# greenhousectrl-latest.net
KiCad netlist of a schematic drawn in EAGLE
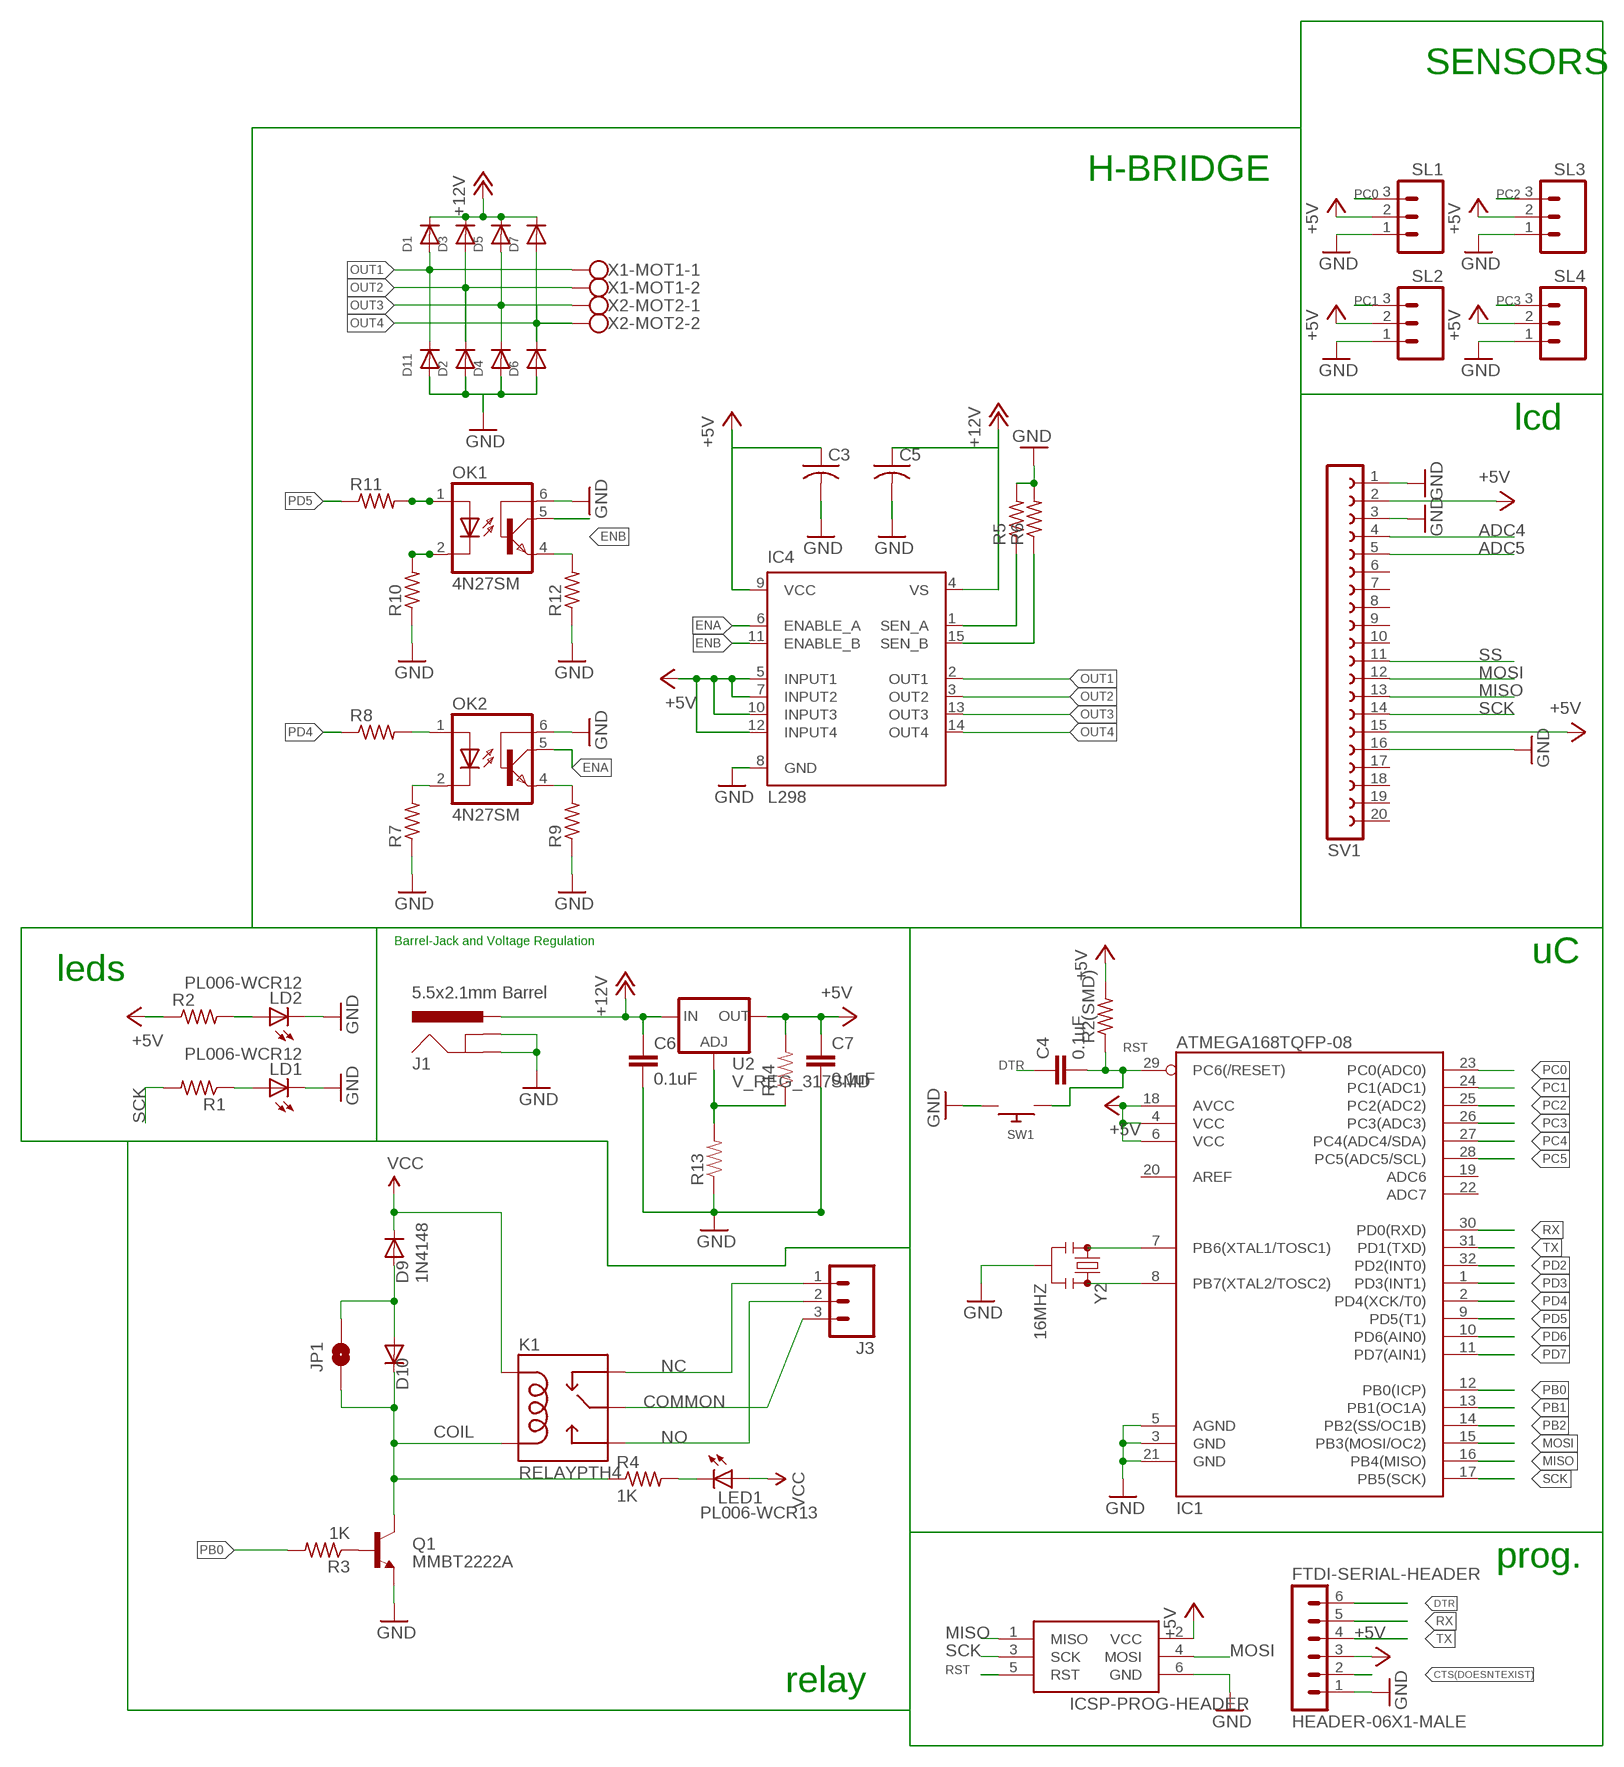
[diagram p0: schematic, sheet 1]

(export (version "E")
  (design (tool "Eeschema 10.0.6"))
  (components
    (comp (ref "C3")
      (value "C-US025-024X044")
      (footprint "eagle-import:C025-024X044")
      (libsource (lib "eagle-import") (part "C-US025-024X044"))
    )
    (comp (ref "C4")
      (value "0.1uF")
      (footprint "eagle-import:0603-CAP")
      (libsource (lib "eagle-import") (part "0.1UF-25V(+80/-20%)(0603)"))
    )
    (comp (ref "C5")
      (value "C-US025-024X044")
      (footprint "eagle-import:C025-024X044")
      (libsource (lib "eagle-import") (part "C-US025-024X044"))
    )
    (comp (ref "C6")
      (value "0.1uF")
      (footprint "eagle-import:0603-CAP")
      (libsource (lib "eagle-import") (part "0.1UF-25V(+80/-20%)(0603)"))
    )
    (comp (ref "C7")
      (value "0.1uF")
      (footprint "eagle-import:0603-CAP")
      (libsource (lib "eagle-import") (part "0.1UF-25V(+80/-20%)(0603)"))
    )
    (comp (ref "D1")
      (value "DIODESOD-523")
      (footprint "eagle-import:SOD-523")
      (libsource (lib "eagle-import") (part "DIODESOD-523"))
    )
    (comp (ref "D2")
      (value "DIODESOD-523")
      (footprint "eagle-import:SOD-523")
      (libsource (lib "eagle-import") (part "DIODESOD-523"))
    )
    (comp (ref "D3")
      (value "DIODESOD-523")
      (footprint "eagle-import:SOD-523")
      (libsource (lib "eagle-import") (part "DIODESOD-523"))
    )
    (comp (ref "D4")
      (value "DIODESOD-523")
      (footprint "eagle-import:SOD-523")
      (libsource (lib "eagle-import") (part "DIODESOD-523"))
    )
    (comp (ref "D5")
      (value "DIODESOD-523")
      (footprint "eagle-import:SOD-523")
      (libsource (lib "eagle-import") (part "DIODESOD-523"))
    )
    (comp (ref "D6")
      (value "DIODESOD-523")
      (footprint "eagle-import:SOD-523")
      (libsource (lib "eagle-import") (part "DIODESOD-523"))
    )
    (comp (ref "D7")
      (value "DIODESOD-523")
      (footprint "eagle-import:SOD-523")
      (libsource (lib "eagle-import") (part "DIODESOD-523"))
    )
    (comp (ref "D9")
      (value "1N4148")
      (footprint "eagle-import:SOD-323F")
      (libsource (lib "eagle-import") (part "DIODESOD-323F"))
    )
    (comp (ref "D10")
      (value "Zener")
      (footprint "eagle-import:SOD-323F")
      (libsource (lib "eagle-import") (part "DIODESOD-323F"))
    )
    (comp (ref "D11")
      (value "DIODESOD-523")
      (footprint "eagle-import:SOD-523")
      (libsource (lib "eagle-import") (part "DIODESOD-523"))
    )
    (comp (ref "FTDI-SERIAL-HEADER")
      (value "HEADER-06X1-MALE")
      (footprint "eagle-import:06X1-PTH")
      (libsource (lib "eagle-import") (part "HEADER-06X1?-MALE"))
    )
    (comp (ref "IC1")
      (value "ATMEGA168TQFP-08")
      (footprint "eagle-import:TQFP32-08")
      (libsource (lib "eagle-import") (part "ATMEGA168TQFP-08"))
    )
    (comp (ref "IC4")
      (value "L298")
      (footprint "eagle-import:MULTIWATT-15")
      (fields (field (name "MPN") "L298N"))
      (libsource (lib "eagle-import") (part "L298"))
    )
    (comp (ref "ICSP-PROG-HEADER")
      (value "AVRISP-6")
      (footprint "eagle-import:AVRISP")
      (libsource (lib "eagle-import") (part "AVRISP-6"))
    )
    (comp (ref "J1")
      (value "5.5x2.1mm Barrel")
      (footprint "eagle-import:POWER_JACK_SMD")
      (libsource (lib "eagle-import") (part "POWER_JACKSMD"))
    )
    (comp (ref "J3")
      (value "M03-SCREW-5MM")
      (footprint "eagle-import:SCREWTERMINAL-5MM-3")
      (libsource (lib "eagle-import") (part "M03-SCREW-5MM"))
    )
    (comp (ref "JP1")
      (value "JUMPER-PAD-2-NOYES_SILK")
      (footprint "eagle-import:PAD-JUMPER-2-NO_YES_SILK")
      (libsource (lib "eagle-import") (part "JUMPER-PAD-2-NOYES_SILK"))
    )
    (comp (ref "K1")
      (value "RELAYPTH4")
      (footprint "eagle-import:RELAY-JZC")
      (libsource (lib "eagle-import") (part "RELAYPTH4"))
    )
    (comp (ref "LD1")
      (value "PL006-WCR12")
      (footprint "eagle-import:SOT23")
      (libsource (lib "eagle-import") (part "PL006-WCR12"))
    )
    (comp (ref "LD2")
      (value "PL006-WCR12")
      (footprint "eagle-import:SOT23")
      (libsource (lib "eagle-import") (part "PL006-WCR12"))
    )
    (comp (ref "LED1")
      (value "PL006-WCR13")
      (footprint "eagle-import:SOT23")
      (fields (field (name "PROD_ID") "DIO-09529"))
      (libsource (lib "eagle-import") (part "PL006-WCR13"))
    )
    (comp (ref "OK1")
      (value "4N27SM")
      (footprint "eagle-import:DIL6-SMD")
      (fields (field (name "MF") "FAIRCHILD SEMICONDUCTOR") (field (name "MPN") "4N27S-M"))
      (libsource (lib "eagle-import") (part "4N?MS27"))
    )
    (comp (ref "OK2")
      (value "4N27SM")
      (footprint "eagle-import:DIL6-SMD")
      (fields (field (name "MF") "FAIRCHILD SEMICONDUCTOR") (field (name "MPN") "4N27S-M"))
      (libsource (lib "eagle-import") (part "4N?MS27"))
    )
    (comp (ref "Q1")
      (value "MMBT2222A")
      (footprint "eagle-import:SOT23-3")
      (libsource (lib "eagle-import") (part "TRANSISTOR_NPNMMBT2222A"))
    )
    (comp (ref "R1")
      (value "R-US_M0805")
      (footprint "eagle-import:M0805")
      (libsource (lib "eagle-import") (part "R-US_M0805"))
    )
    (comp (ref "R2")
      (value "R-US_M0805")
      (footprint "eagle-import:M0805")
      (libsource (lib "eagle-import") (part "R-US_M0805"))
    )
    (comp (ref "R2(SMD)")
      (value "R-US_M0805")
      (footprint "eagle-import:M0805")
      (libsource (lib "eagle-import") (part "R-US_M0805"))
    )
    (comp (ref "R3")
      (value "1K")
      (footprint "eagle-import:M0805")
      (libsource (lib "eagle-import") (part "R-US_M0805"))
    )
    (comp (ref "R4")
      (value "1K")
      (footprint "eagle-import:M0805")
      (libsource (lib "eagle-import") (part "R-US_M0805"))
    )
    (comp (ref "R5")
      (value "R-US_M0805")
      (footprint "eagle-import:M0805")
      (libsource (lib "eagle-import") (part "R-US_M0805"))
    )
    (comp (ref "R6")
      (value "R-US_M0805")
      (footprint "eagle-import:M0805")
      (libsource (lib "eagle-import") (part "R-US_M0805"))
    )
    (comp (ref "R7")
      (value "R-US_M0805")
      (footprint "eagle-import:M0805")
      (libsource (lib "eagle-import") (part "R-US_M0805"))
    )
    (comp (ref "R8")
      (value "R-US_M0805")
      (footprint "eagle-import:M0805")
      (libsource (lib "eagle-import") (part "R-US_M0805"))
    )
    (comp (ref "R9")
      (value "R-US_M0805")
      (footprint "eagle-import:M0805")
      (libsource (lib "eagle-import") (part "R-US_M0805"))
    )
    (comp (ref "R10")
      (value "R-US_M0805")
      (footprint "eagle-import:M0805")
      (libsource (lib "eagle-import") (part "R-US_M0805"))
    )
    (comp (ref "R11")
      (value "R-US_M0805")
      (footprint "eagle-import:M0805")
      (libsource (lib "eagle-import") (part "R-US_M0805"))
    )
    (comp (ref "R12")
      (value "R-US_M0805")
      (footprint "eagle-import:M0805")
      (libsource (lib "eagle-import") (part "R-US_M0805"))
    )
    (comp (ref "R13")
      (value "RESISTOR0402")
      (footprint "eagle-import:0402-RES")
      (libsource (lib "eagle-import") (part "RESISTOR0402"))
    )
    (comp (ref "R14")
      (value "RESISTOR0402")
      (footprint "eagle-import:0402-RES")
      (libsource (lib "eagle-import") (part "RESISTOR0402"))
    )
    (comp (ref "SL1")
      (value "M03")
      (footprint "eagle-import:03P")
      (libsource (lib "eagle-import") (part "M03"))
    )
    (comp (ref "SL2")
      (value "M03")
      (footprint "eagle-import:03P")
      (libsource (lib "eagle-import") (part "M03"))
    )
    (comp (ref "SL3")
      (value "M03")
      (footprint "eagle-import:03P")
      (libsource (lib "eagle-import") (part "M03"))
    )
    (comp (ref "SL4")
      (value "M03")
      (footprint "eagle-import:03P")
      (libsource (lib "eagle-import") (part "M03"))
    )
    (comp (ref "SV1")
      (value "FE20-1")
      (footprint "eagle-import:FE20")
      (libsource (lib "eagle-import") (part "FE20-1"))
    )
    (comp (ref "SW1")
      (value "SWITCH_PUSHBUTTONC&K_KSS")
      (footprint "eagle-import:BTN_CK_KSS")
      (libsource (lib "eagle-import") (part "SWITCH_PUSHBUTTONC&K_KSS"))
    )
    (comp (ref "U2")
      (value "V_REG_317SMD")
      (footprint "eagle-import:SOT223")
      (libsource (lib "eagle-import") (part "V_REG_317SMD"))
    )
    (comp (ref "X1-MOT1")
      (value "W237-102")
      (footprint "eagle-import:W237-102")
      (fields (field (name "MPN") "237-102"))
      (libsource (lib "eagle-import") (part "W237-102"))
    )
    (comp (ref "X2-MOT2")
      (value "W237-102")
      (footprint "eagle-import:W237-102")
      (fields (field (name "MPN") "237-102"))
      (libsource (lib "eagle-import") (part "W237-102"))
    )
    (comp (ref "Y2")
      (value "16MHZ")
      (footprint "eagle-import:RESONATOR-SMD")
      (libsource (lib "eagle-import") (part "RESONATOR16MHZ"))
    )
  )
  (nets
    (net (code "1") (name "+5V") (class "Default")
      (node (ref "C3") (pin "1") (pinfunction "1_1") (pintype "passive"))
      (node (ref "C7") (pin "1") (pinfunction "1_1") (pintype "passive"))
      (node (ref "FTDI-SERIAL-HEADER") (pin "3") (pinfunction "3_3") (pintype "passive"))
      (node (ref "IC1") (pin "18") (pinfunction "AVCC_18") (pintype "bidirectional"))
      (node (ref "IC1") (pin "4") (pinfunction "VCC_4") (pintype "bidirectional"))
      (node (ref "IC1") (pin "6") (pinfunction "VCC_6") (pintype "bidirectional"))
      (node (ref "IC4") (pin "10") (pinfunction "INPUT3_10") (pintype "input"))
      (node (ref "IC4") (pin "12") (pinfunction "INPUT4_12") (pintype "input"))
      (node (ref "IC4") (pin "5") (pinfunction "INPUT1_5") (pintype "input"))
      (node (ref "IC4") (pin "7") (pinfunction "INPUT2_7") (pintype "input"))
      (node (ref "IC4") (pin "9") (pinfunction "VCC_9") (pintype "power_in"))
      (node (ref "ICSP-PROG-HEADER") (pin "2") (pinfunction "VCC_2") (pintype "power_in"))
      (node (ref "R14") (pin "2") (pinfunction "2_2") (pintype "passive"))
      (node (ref "R2") (pin "1") (pinfunction "1_1") (pintype "passive"))
      (node (ref "R2(SMD)") (pin "2") (pinfunction "2_2") (pintype "passive"))
      (node (ref "SL1") (pin "2") (pinfunction "2_2") (pintype "passive"))
      (node (ref "SL2") (pin "2") (pinfunction "2_2") (pintype "passive"))
      (node (ref "SL3") (pin "2") (pinfunction "2_2") (pintype "passive"))
      (node (ref "SL4") (pin "2") (pinfunction "2_2") (pintype "passive"))
      (node (ref "SV1") (pin "15") (pinfunction "15_15") (pintype "passive"))
      (node (ref "SV1") (pin "2") (pinfunction "2_2") (pintype "passive"))
      (node (ref "U2") (pin "2") (pinfunction "OUT_2") (pintype "output"))
    )
    (net (code "2") (name "+12V") (class "Default")
      (node (ref "C5") (pin "1") (pinfunction "1_1") (pintype "passive"))
      (node (ref "C6") (pin "1") (pinfunction "1_1") (pintype "passive"))
      (node (ref "D1") (pin "K") (pinfunction "C_K") (pintype "passive"))
      (node (ref "D3") (pin "K") (pinfunction "C_K") (pintype "passive"))
      (node (ref "D5") (pin "K") (pinfunction "C_K") (pintype "passive"))
      (node (ref "D7") (pin "K") (pinfunction "C_K") (pintype "passive"))
      (node (ref "IC4") (pin "4") (pinfunction "VS_4") (pintype "power_in"))
      (node (ref "J1") (pin "VIN0") (pinfunction "PWR_VIN0") (pintype "bidirectional"))
      (node (ref "U2") (pin "3") (pinfunction "IN_3") (pintype "input"))
    )
    (net (code "3") (name "/ADC4") (class "Default")
      (node (ref "SV1") (pin "4") (pinfunction "4_4") (pintype "passive"))
    )
    (net (code "4") (name "/ADC5") (class "Default")
      (node (ref "SV1") (pin "5") (pinfunction "5_5") (pintype "passive"))
    )
    (net (code "5") (name "/COIL") (class "Default")
      (node (ref "D10") (pin "C") (pinfunction "C_C") (pintype "passive"))
      (node (ref "JP1") (pin "1") (pinfunction "1_1") (pintype "passive"))
      (node (ref "K1") (pin "1") (pinfunction "COIL2_1") (pintype "bidirectional"))
      (node (ref "Q1") (pin "3") (pinfunction "C_3") (pintype "passive"))
      (node (ref "R4") (pin "1") (pinfunction "1_1") (pintype "passive"))
    )
    (net (code "6") (name "/COMMON") (class "Default")
      (node (ref "J3") (pin "3") (pinfunction "3_3") (pintype "passive"))
      (node (ref "K1") (pin "4") (pinfunction "MAIN_4") (pintype "bidirectional"))
    )
    (net (code "7") (name "/NC") (class "Default")
      (node (ref "J3") (pin "1") (pinfunction "1_1") (pintype "passive"))
      (node (ref "K1") (pin "2") (pinfunction "NC_2") (pintype "bidirectional"))
    )
    (net (code "8") (name "/NO") (class "Default")
      (node (ref "J3") (pin "2") (pinfunction "2_2") (pintype "passive"))
      (node (ref "K1") (pin "3") (pinfunction "NO_3") (pintype "bidirectional"))
    )
    (net (code "9") (name "/RST") (class "Default")
      (node (ref "C4") (pin "2") (pinfunction "2_2") (pintype "passive"))
      (node (ref "IC1") (pin "29") (pinfunction "PC6(/RESET)_29") (pintype "bidirectional"))
      (node (ref "ICSP-PROG-HEADER") (pin "5") (pinfunction "RST_5") (pintype "output"))
      (node (ref "R2(SMD)") (pin "1") (pinfunction "1_1") (pintype "passive"))
      (node (ref "SW1") (pin "P$1") (pinfunction "P$1_P$1") (pintype "passive"))
    )
    (net (code "10") (name "/SS") (class "Default")
      (node (ref "SV1") (pin "11") (pinfunction "11_11") (pintype "passive"))
    )
    (net (code "11") (name "CTS(DOESNTEXIST)") (class "Default")
      (node (ref "FTDI-SERIAL-HEADER") (pin "2") (pinfunction "2_2") (pintype "passive"))
    )
    (net (code "12") (name "DTR") (class "Default")
      (node (ref "C4") (pin "1") (pinfunction "1_1") (pintype "passive"))
      (node (ref "FTDI-SERIAL-HEADER") (pin "6") (pinfunction "6_6") (pintype "passive"))
    )
    (net (code "13") (name "ENA") (class "Default")
      (node (ref "IC4") (pin "6") (pinfunction "ENABLE_A_6") (pintype "input"))
      (node (ref "OK2") (pin "5") (pinfunction "COL_5") (pintype "passive"))
    )
    (net (code "14") (name "ENB") (class "Default")
      (node (ref "IC4") (pin "11") (pinfunction "ENABLE_B_11") (pintype "input"))
      (node (ref "OK1") (pin "5") (pinfunction "COL_5") (pintype "passive"))
    )
    (net (code "15") (name "GND") (class "Default")
      (node (ref "C3") (pin "2") (pinfunction "2_2") (pintype "passive"))
      (node (ref "C5") (pin "2") (pinfunction "2_2") (pintype "passive"))
      (node (ref "C6") (pin "2") (pinfunction "2_2") (pintype "passive"))
      (node (ref "C7") (pin "2") (pinfunction "2_2") (pintype "passive"))
      (node (ref "D11") (pin "A") (pinfunction "A_A") (pintype "passive"))
      (node (ref "D2") (pin "A") (pinfunction "A_A") (pintype "passive"))
      (node (ref "D4") (pin "A") (pinfunction "A_A") (pintype "passive"))
      (node (ref "D6") (pin "A") (pinfunction "A_A") (pintype "passive"))
      (node (ref "FTDI-SERIAL-HEADER") (pin "1") (pinfunction "1_1") (pintype "passive"))
      (node (ref "IC1") (pin "21") (pinfunction "GND_21") (pintype "bidirectional"))
      (node (ref "IC1") (pin "3") (pinfunction "GND_3") (pintype "bidirectional"))
      (node (ref "IC1") (pin "5") (pinfunction "AGND_5") (pintype "bidirectional"))
      (node (ref "IC4") (pin "8") (pinfunction "GND_8") (pintype "power_in"))
      (node (ref "ICSP-PROG-HEADER") (pin "6") (pinfunction "GND_6") (pintype "power_in"))
      (node (ref "J1") (pin "GND") (pinfunction "GNDBREAK_GND") (pintype "bidirectional"))
      (node (ref "J1") (pin "P$4") (pinfunction "GND_P$4") (pintype "bidirectional"))
      (node (ref "LD1") (pin "3") (pinfunction "C_3") (pintype "passive"))
      (node (ref "LD2") (pin "3") (pinfunction "C_3") (pintype "passive"))
      (node (ref "OK1") (pin "6") (pinfunction "BAS_6") (pintype "passive"))
      (node (ref "OK2") (pin "6") (pinfunction "BAS_6") (pintype "passive"))
      (node (ref "Q1") (pin "2") (pinfunction "E_2") (pintype "passive"))
      (node (ref "R10") (pin "1") (pinfunction "1_1") (pintype "passive"))
      (node (ref "R12") (pin "1") (pinfunction "1_1") (pintype "passive"))
      (node (ref "R13") (pin "1") (pinfunction "1_1") (pintype "passive"))
      (node (ref "R5") (pin "2") (pinfunction "2_2") (pintype "passive"))
      (node (ref "R6") (pin "2") (pinfunction "2_2") (pintype "passive"))
      (node (ref "R7") (pin "1") (pinfunction "1_1") (pintype "passive"))
      (node (ref "R9") (pin "1") (pinfunction "1_1") (pintype "passive"))
      (node (ref "SL1") (pin "1") (pinfunction "1_1") (pintype "passive"))
      (node (ref "SL2") (pin "1") (pinfunction "1_1") (pintype "passive"))
      (node (ref "SL3") (pin "1") (pinfunction "1_1") (pintype "passive"))
      (node (ref "SL4") (pin "1") (pinfunction "1_1") (pintype "passive"))
      (node (ref "SV1") (pin "1") (pinfunction "1_1") (pintype "passive"))
      (node (ref "SV1") (pin "16") (pinfunction "16_16") (pintype "passive"))
      (node (ref "SV1") (pin "3") (pinfunction "3_3") (pintype "passive"))
      (node (ref "SW1") (pin "P$2") (pinfunction "P$2_P$2") (pintype "passive"))
      (node (ref "Y2") (pin "2") (pinfunction "2_2") (pintype "passive"))
    )
    (net (code "16") (name "MISO") (class "Default")
      (node (ref "IC1") (pin "16") (pinfunction "PB4(MISO)_16") (pintype "bidirectional"))
      (node (ref "ICSP-PROG-HEADER") (pin "1") (pinfunction "MISO_1") (pintype "input"))
      (node (ref "SV1") (pin "13") (pinfunction "13_13") (pintype "passive"))
    )
    (net (code "17") (name "MOSI") (class "Default")
      (node (ref "IC1") (pin "15") (pinfunction "PB3(MOSI/OC2)_15") (pintype "bidirectional"))
      (node (ref "ICSP-PROG-HEADER") (pin "4") (pinfunction "MOSI_4") (pintype "output"))
      (node (ref "SV1") (pin "12") (pinfunction "12_12") (pintype "passive"))
    )
    (net (code "18") (name "Net-(D10-PadA)") (class "Default")
      (node (ref "D10") (pin "A") (pinfunction "A_A") (pintype "passive"))
      (node (ref "D9") (pin "A") (pinfunction "A_A") (pintype "passive"))
      (node (ref "JP1") (pin "2") (pinfunction "2_2") (pintype "passive"))
    )
    (net (code "19") (name "Net-(IC1-PB6(XTAL1{slash}TOSC1))") (class "Default")
      (node (ref "IC1") (pin "7") (pinfunction "PB6(XTAL1/TOSC1)_7") (pintype "bidirectional"))
      (node (ref "Y2") (pin "1") (pinfunction "1_1") (pintype "passive"))
    )
    (net (code "20") (name "Net-(IC1-PB7(XTAL2{slash}TOSC2))") (class "Default")
      (node (ref "IC1") (pin "8") (pinfunction "PB7(XTAL2/TOSC2)_8") (pintype "bidirectional"))
      (node (ref "Y2") (pin "3") (pinfunction "3_3") (pintype "passive"))
    )
    (net (code "21") (name "Net-(IC4-SEN_A)") (class "Default")
      (node (ref "IC4") (pin "1") (pinfunction "SEN_A_1") (pintype "input"))
      (node (ref "R5") (pin "1") (pinfunction "1_1") (pintype "passive"))
    )
    (net (code "22") (name "Net-(IC4-SEN_B)") (class "Default")
      (node (ref "IC4") (pin "15") (pinfunction "SEN_B_15") (pintype "input"))
      (node (ref "R6") (pin "1") (pinfunction "1_1") (pintype "passive"))
    )
    (net (code "23") (name "Net-(LD1-A)") (class "Default")
      (node (ref "LD1") (pin "1") (pinfunction "A_1") (pintype "passive"))
      (node (ref "R1") (pin "1") (pinfunction "1_1") (pintype "passive"))
    )
    (net (code "24") (name "Net-(LD2-A)") (class "Default")
      (node (ref "LD2") (pin "1") (pinfunction "A_1") (pintype "passive"))
      (node (ref "R2") (pin "2") (pinfunction "2_2") (pintype "passive"))
    )
    (net (code "25") (name "Net-(LED1-C)") (class "Default")
      (node (ref "LED1") (pin "3") (pinfunction "C_3") (pintype "passive"))
      (node (ref "R4") (pin "2") (pinfunction "2_2") (pintype "passive"))
    )
    (net (code "26") (name "Net-(OK1-A)") (class "Default")
      (node (ref "OK1") (pin "1") (pinfunction "A_1") (pintype "passive"))
      (node (ref "R11") (pin "2") (pinfunction "2_2") (pintype "passive"))
    )
    (net (code "27") (name "Net-(OK1-C)") (class "Default")
      (node (ref "OK1") (pin "2") (pinfunction "C_2") (pintype "passive"))
      (node (ref "R10") (pin "2") (pinfunction "2_2") (pintype "passive"))
    )
    (net (code "28") (name "Net-(OK1-EMI)") (class "Default")
      (node (ref "OK1") (pin "4") (pinfunction "EMI_4") (pintype "passive"))
      (node (ref "R12") (pin "2") (pinfunction "2_2") (pintype "passive"))
    )
    (net (code "29") (name "Net-(OK2-A)") (class "Default")
      (node (ref "OK2") (pin "1") (pinfunction "A_1") (pintype "passive"))
      (node (ref "R8") (pin "2") (pinfunction "2_2") (pintype "passive"))
    )
    (net (code "30") (name "Net-(OK2-C)") (class "Default")
      (node (ref "OK2") (pin "2") (pinfunction "C_2") (pintype "passive"))
      (node (ref "R7") (pin "2") (pinfunction "2_2") (pintype "passive"))
    )
    (net (code "31") (name "Net-(OK2-EMI)") (class "Default")
      (node (ref "OK2") (pin "4") (pinfunction "EMI_4") (pintype "passive"))
      (node (ref "R9") (pin "2") (pinfunction "2_2") (pintype "passive"))
    )
    (net (code "32") (name "Net-(Q1-B)") (class "Default")
      (node (ref "Q1") (pin "1") (pinfunction "B_1") (pintype "passive"))
      (node (ref "R3") (pin "1") (pinfunction "1_1") (pintype "passive"))
    )
    (net (code "33") (name "Net-(U2-ADJ)") (class "Default")
      (node (ref "R13") (pin "2") (pinfunction "2_2") (pintype "passive"))
      (node (ref "R14") (pin "1") (pinfunction "1_1") (pintype "passive"))
      (node (ref "U2") (pin "1") (pinfunction "ADJ_1") (pintype "input"))
    )
    (net (code "34") (name "OUT1") (class "Default")
      (node (ref "D1") (pin "A") (pinfunction "A_A") (pintype "passive"))
      (node (ref "D11") (pin "K") (pinfunction "C_K") (pintype "passive"))
      (node (ref "IC4") (pin "2") (pinfunction "OUT1_2") (pintype "output"))
      (node (ref "X1-MOT1") (pin "1") (pinfunction "KL_1") (pintype "passive"))
    )
    (net (code "35") (name "OUT2") (class "Default")
      (node (ref "D2") (pin "K") (pinfunction "C_K") (pintype "passive"))
      (node (ref "D3") (pin "A") (pinfunction "A_A") (pintype "passive"))
      (node (ref "IC4") (pin "3") (pinfunction "OUT2_3") (pintype "output"))
      (node (ref "X1-MOT1") (pin "2") (pinfunction "KL_2") (pintype "passive"))
    )
    (net (code "36") (name "OUT3") (class "Default")
      (node (ref "D4") (pin "K") (pinfunction "C_K") (pintype "passive"))
      (node (ref "D5") (pin "A") (pinfunction "A_A") (pintype "passive"))
      (node (ref "IC4") (pin "13") (pinfunction "OUT3_13") (pintype "output"))
      (node (ref "X2-MOT2") (pin "1") (pinfunction "KL_1") (pintype "passive"))
    )
    (net (code "37") (name "OUT4") (class "Default")
      (node (ref "D6") (pin "K") (pinfunction "C_K") (pintype "passive"))
      (node (ref "D7") (pin "A") (pinfunction "A_A") (pintype "passive"))
      (node (ref "IC4") (pin "14") (pinfunction "OUT4_14") (pintype "output"))
      (node (ref "X2-MOT2") (pin "2") (pinfunction "KL_2") (pintype "passive"))
    )
    (net (code "38") (name "PB0") (class "Default")
      (node (ref "IC1") (pin "12") (pinfunction "PB0(ICP)_12") (pintype "bidirectional"))
      (node (ref "R3") (pin "2") (pinfunction "2_2") (pintype "passive"))
    )
    (net (code "39") (name "PB1") (class "Default")
      (node (ref "IC1") (pin "13") (pinfunction "PB1(OC1A)_13") (pintype "bidirectional"))
    )
    (net (code "40") (name "PB2") (class "Default")
      (node (ref "IC1") (pin "14") (pinfunction "PB2(SS/OC1B)_14") (pintype "bidirectional"))
    )
    (net (code "41") (name "PC0") (class "Default")
      (node (ref "IC1") (pin "23") (pinfunction "PC0(ADC0)_23") (pintype "bidirectional"))
      (node (ref "SL1") (pin "3") (pinfunction "3_3") (pintype "passive"))
    )
    (net (code "42") (name "PC1") (class "Default")
      (node (ref "IC1") (pin "24") (pinfunction "PC1(ADC1)_24") (pintype "bidirectional"))
      (node (ref "SL2") (pin "3") (pinfunction "3_3") (pintype "passive"))
    )
    (net (code "43") (name "PC2") (class "Default")
      (node (ref "IC1") (pin "25") (pinfunction "PC2(ADC2)_25") (pintype "bidirectional"))
      (node (ref "SL3") (pin "3") (pinfunction "3_3") (pintype "passive"))
    )
    (net (code "44") (name "PC3") (class "Default")
      (node (ref "IC1") (pin "26") (pinfunction "PC3(ADC3)_26") (pintype "bidirectional"))
      (node (ref "SL4") (pin "3") (pinfunction "3_3") (pintype "passive"))
    )
    (net (code "45") (name "PC4") (class "Default")
      (node (ref "IC1") (pin "27") (pinfunction "PC4(ADC4/SDA)_27") (pintype "bidirectional"))
    )
    (net (code "46") (name "PC5") (class "Default")
      (node (ref "IC1") (pin "28") (pinfunction "PC5(ADC5/SCL)_28") (pintype "bidirectional"))
    )
    (net (code "47") (name "PD2") (class "Default")
      (node (ref "IC1") (pin "32") (pinfunction "PD2(INT0)_32") (pintype "bidirectional"))
    )
    (net (code "48") (name "PD3") (class "Default")
      (node (ref "IC1") (pin "1") (pinfunction "PD3(INT1)_1") (pintype "bidirectional"))
    )
    (net (code "49") (name "PD4") (class "Default")
      (node (ref "IC1") (pin "2") (pinfunction "PD4(XCK/T0)_2") (pintype "bidirectional"))
      (node (ref "R8") (pin "1") (pinfunction "1_1") (pintype "passive"))
    )
    (net (code "50") (name "PD5") (class "Default")
      (node (ref "IC1") (pin "9") (pinfunction "PD5(T1)_9") (pintype "bidirectional"))
      (node (ref "R11") (pin "1") (pinfunction "1_1") (pintype "passive"))
    )
    (net (code "51") (name "PD6") (class "Default")
      (node (ref "IC1") (pin "10") (pinfunction "PD6(AIN0)_10") (pintype "bidirectional"))
    )
    (net (code "52") (name "PD7") (class "Default")
      (node (ref "IC1") (pin "11") (pinfunction "PD7(AIN1)_11") (pintype "bidirectional"))
    )
    (net (code "53") (name "RX") (class "Default")
      (node (ref "FTDI-SERIAL-HEADER") (pin "5") (pinfunction "5_5") (pintype "passive"))
      (node (ref "IC1") (pin "30") (pinfunction "PD0(RXD)_30") (pintype "bidirectional"))
    )
    (net (code "54") (name "SCK") (class "Default")
      (node (ref "IC1") (pin "17") (pinfunction "PB5(SCK)_17") (pintype "bidirectional"))
      (node (ref "ICSP-PROG-HEADER") (pin "3") (pinfunction "SCK_3") (pintype "output"))
      (node (ref "R1") (pin "2") (pinfunction "2_2") (pintype "passive"))
      (node (ref "SV1") (pin "14") (pinfunction "14_14") (pintype "passive"))
    )
    (net (code "55") (name "TX") (class "Default")
      (node (ref "FTDI-SERIAL-HEADER") (pin "4") (pinfunction "4_4") (pintype "passive"))
      (node (ref "IC1") (pin "31") (pinfunction "PD1(TXD)_31") (pintype "bidirectional"))
    )
    (net (code "56") (name "VCC") (class "Default")
      (node (ref "D9") (pin "C") (pinfunction "C_C") (pintype "passive"))
      (node (ref "K1") (pin "5") (pinfunction "COIL1_5") (pintype "bidirectional"))
      (node (ref "LED1") (pin "1") (pinfunction "A_1") (pintype "passive"))
    )
    (net (code "57") (name "unconnected-(IC1-ADC6-Pad19)") (class "Default")
      (node (ref "IC1") (pin "19") (pinfunction "ADC6_19") (pintype "bidirectional"))
    )
    (net (code "58") (name "unconnected-(IC1-ADC7-Pad22)") (class "Default")
      (node (ref "IC1") (pin "22") (pinfunction "ADC7_22") (pintype "bidirectional"))
    )
    (net (code "59") (name "unconnected-(IC1-AREF-Pad20)") (class "Default")
      (node (ref "IC1") (pin "20") (pinfunction "AREF_20") (pintype "bidirectional"))
    )
    (net (code "60") (name "unconnected-(SV1-Pad6)") (class "Default")
      (node (ref "SV1") (pin "6") (pinfunction "6_6") (pintype "passive"))
    )
    (net (code "61") (name "unconnected-(SV1-Pad7)") (class "Default")
      (node (ref "SV1") (pin "7") (pinfunction "7_7") (pintype "passive"))
    )
    (net (code "62") (name "unconnected-(SV1-Pad8)") (class "Default")
      (node (ref "SV1") (pin "8") (pinfunction "8_8") (pintype "passive"))
    )
    (net (code "63") (name "unconnected-(SV1-Pad9)") (class "Default")
      (node (ref "SV1") (pin "9") (pinfunction "9_9") (pintype "passive"))
    )
    (net (code "64") (name "unconnected-(SV1-Pad10)") (class "Default")
      (node (ref "SV1") (pin "10") (pinfunction "10_10") (pintype "passive"))
    )
    (net (code "65") (name "unconnected-(SV1-Pad17)") (class "Default")
      (node (ref "SV1") (pin "17") (pinfunction "17_17") (pintype "passive"))
    )
    (net (code "66") (name "unconnected-(SV1-Pad18)") (class "Default")
      (node (ref "SV1") (pin "18") (pinfunction "18_18") (pintype "passive"))
    )
    (net (code "67") (name "unconnected-(SV1-Pad19)") (class "Default")
      (node (ref "SV1") (pin "19") (pinfunction "19_19") (pintype "passive"))
    )
    (net (code "68") (name "unconnected-(SV1-Pad20)") (class "Default")
      (node (ref "SV1") (pin "20") (pinfunction "20_20") (pintype "passive"))
    )
  )
)
